# MCU.net
KiCad netlist of a schematic drawn in Altium Designer
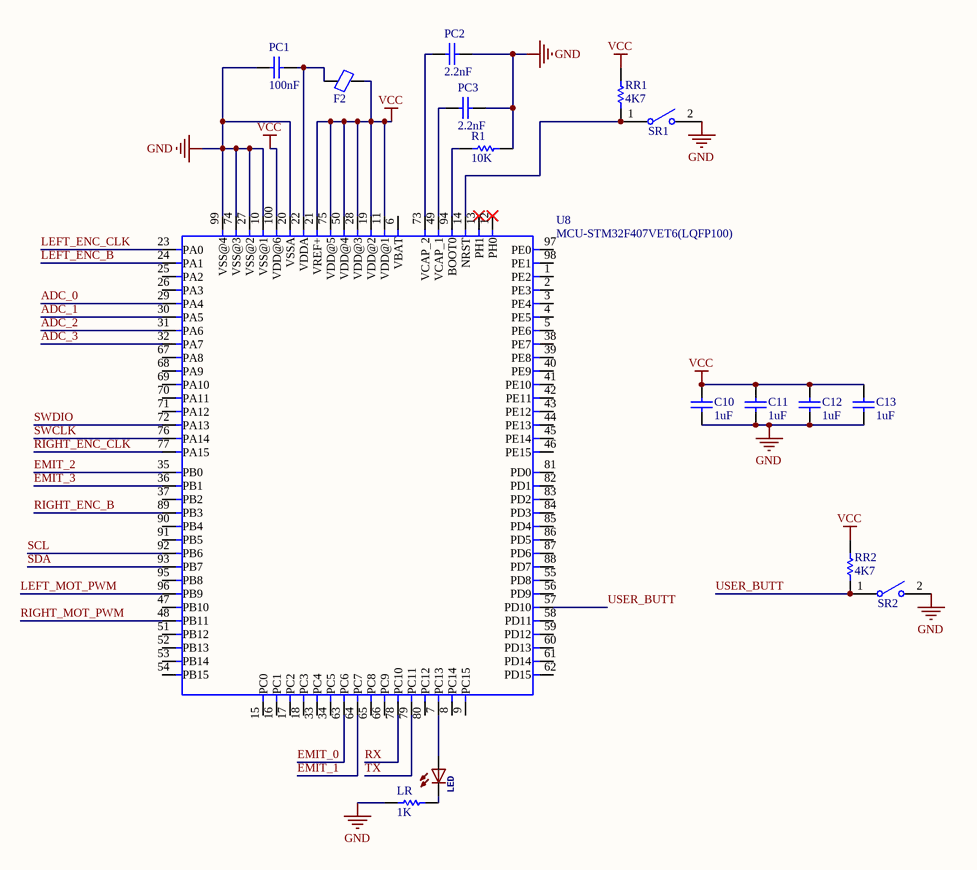
[diagram p0: MCU.SchDoc]

(export (version "E")
  (design (tool "Eeschema 10.0.6"))
  (components
    (comp (ref "C10")
      (value "1uF")
      (footprint "CAP0603")
      (description "0603 CAPACITOR SMD")
      (fields (field (name "DESIGNER") "Abbas Basereh"))
      (libsource (lib "Altium") (part "CAP SMD PACKAGE"))
    )
    (comp (ref "C11")
      (value "1uF")
      (footprint "CAP0603")
      (description "0603 CAPACITOR SMD")
      (fields (field (name "DESIGNER") "Abbas Basereh"))
      (libsource (lib "Altium") (part "CAP SMD PACKAGE"))
    )
    (comp (ref "C12")
      (value "1uF")
      (footprint "CAP0603")
      (description "0603 CAPACITOR SMD")
      (fields (field (name "DESIGNER") "Abbas Basereh"))
      (libsource (lib "Altium") (part "CAP SMD PACKAGE"))
    )
    (comp (ref "C13")
      (value "1uF")
      (footprint "CAP0603")
      (description "0603 CAPACITOR SMD")
      (fields (field (name "DESIGNER") "Abbas Basereh"))
      (libsource (lib "Altium") (part "CAP SMD PACKAGE"))
    )
    (comp (ref "F2")
      (value "Ferrite Bead SMD")
      (footprint "FB0603")
      (fields (field (name "DESIGNER") "Ali Hafizi"))
      (libsource (lib "Altium") (part "Ferrite Bead SMD Package"))
    )
    (comp (ref "LED")
      (value "LED   OSRAM: - CHIPLED LG R971, LG N971, LY N971, LG Q971, LY Q971, LO R971, LY R971 LH N974, LH R974 LS Q976, LO Q976, LY Q976 LO Q996 - Hyper CHIPLED LW Q18S LB Q993, LB Q99A, LB R99A - SideLED LS A670, LO A670, LY A670, LG A670, LP A670 LB A673, LV A673, LT A673, LW A673 LH A674 LY A675 LS A676, LA A676, LO A676, LY A676, LW A676 LS A679, LY A679, LG A679 -  Hyper Micro SIDELEDÂ® LS Y876, LA Y876, LO Y876, LY Y876 LT Y87S - SmartLED LW L88C, LW L88S LB L89C, LB L89S, LG L890 LS L89K, LO L89K, LY L89K LS L896, LA L896, LO L896, LY L896 - TOPLED LS T670, LO T670, LY T670, LG T670, LP T670 LSG T670, LSP T670, LSY T670, LOP T670, LYG T670 LG T671, LOG T671, LSG T671 LB T673, LV T673, LT T673, LW T673 LH T674 LS T676, LA T676, LO T676, LY T676, LB T676, LH T676, LSB T676, LW T676 LB T67C, LV T67C, LT T67C, LS T67K, LO T67K, LY T67K, LW E67C LS E67B, LA E67B, LO E67B, LY E67B, LB E67C, LV E67C, LT E67C LW T67C LS T679, LY T679, LG T679 LS T770, LO T770, LY T770, LG T770, LP T770 LB T773, LV T773, LT T773, LW T773 LH T774 LS E675, LA E675, LY E675, LS T675 LS T776, LA T776, LO T776, LY T776, LB T776 LHGB T686 LT T68C, LB T68C - Hyper Mini TOPLEDÂ® LB M676 - Mini TOPLED SantanaÂ® LG M470 LS M47K, LO M47K, LY M47K    Source: http://www.osram.convergy.de/")
      (footprint "CHIPLED_0603")
      (libsource (lib "adafruit") (part "LEDCHIPLED_0603"))
    )
    (comp (ref "LR")
      (value "1K")
      (footprint "RES0603")
      (description "TOTAL SMD RESISTOR PACK")
      (fields (field (name "DESIGNER") "Abbas Basereh"))
      (libsource (lib "Altium") (part "RES SMD PACKAGE"))
    )
    (comp (ref "PC1")
      (value "100nF")
      (footprint "CAP0603")
      (description "TOTAL CAPACITOR SMD PACK")
      (fields (field (name "DESIGNER") "Abbas Basereh"))
      (libsource (lib "Altium") (part "CAP SMD PACKAGE"))
    )
    (comp (ref "PC2")
      (value "2.2nF")
      (footprint "CAP0603")
      (description "TOTAL CAPACITOR SMD PACK")
      (fields (field (name "DESIGNER") "Abbas Basereh"))
      (libsource (lib "Altium") (part "CAP SMD PACKAGE"))
    )
    (comp (ref "PC3")
      (value "2.2nF")
      (footprint "CAP0603")
      (description "TOTAL CAPACITOR SMD PACK")
      (fields (field (name "DESIGNER") "Abbas Basereh"))
      (libsource (lib "Altium") (part "CAP SMD PACKAGE"))
    )
    (comp (ref "R1")
      (value "10K")
      (footprint "RES0603")
      (description "TOTAL SMD RESISTOR PACK")
      (fields (field (name "DESIGNER") "Abbas Basereh"))
      (libsource (lib "Altium") (part "RES SMD PACKAGE"))
    )
    (comp (ref "RR1")
      (value "4K7")
      (footprint "RES0603")
      (description "0603 RESISTOR")
      (fields (field (name "DESIGNER") "Abbas Basereh"))
      (libsource (lib "Altium") (part "RES SMD PACKAGE"))
    )
    (comp (ref "RR2")
      (value "4K7")
      (footprint "RES0603")
      (description "0603 RESISTOR")
      (fields (field (name "DESIGNER") "Abbas Basereh"))
      (libsource (lib "Altium") (part "RES SMD PACKAGE"))
    )
    (comp (ref "SR1")
      (value "434113050826")
      (footprint "4341x30508x6_6x3.5x5")
      (description "WS-TASV 6.0x3.5mm Tact Switch, J-Bend SMD version")
      (fields (field (name "PUBLISHER") "Wurth Elektronik"))
      (libsource (lib "Switch - Tactile SMT") (part "434113050826"))
    )
    (comp (ref "SR2")
      (value "434113050826")
      (footprint "4341x30508x6_6x3.5x5")
      (description "WS-TASV 6.0x3.5mm Tact Switch, J-Bend SMD version")
      (fields (field (name "PUBLISHER") "Wurth Elektronik"))
      (libsource (lib "Switch - Tactile SMT") (part "434113050826"))
    )
    (comp (ref "U8")
      (value "MCU-STM32F407VET6(LQFP100)")
      (footprint "LQFP100-0.5-13.8X13.8MM")
      (description "ARMÂ® CortexÂ®-M4 STM32F4 Microcontroller IC 32-Bit 168MHz 512KB _512K x 8_ FLASH 100-LQFP _14x14_")
      (fields (field (name "MF") "STMicroelectronics") (field (name "MP") "STM32F407VET6"))
      (libsource (lib "MCU-STM32F407VET6_LQFP100_") (part "MCU-STM32F407VET6(LQFP100)"))
    )
  )
  (nets
    (net (code "1") (name "/ADC_0") (class "Default")
      (node (ref "U8") (pin "29") (pinfunction "PA4_29") (pintype "bidirectional"))
    )
    (net (code "2") (name "/ADC_1") (class "Default")
      (node (ref "U8") (pin "30") (pinfunction "PA5_30") (pintype "bidirectional"))
    )
    (net (code "3") (name "/ADC_2") (class "Default")
      (node (ref "U8") (pin "31") (pinfunction "PA6_31") (pintype "bidirectional"))
    )
    (net (code "4") (name "/ADC_3") (class "Default")
      (node (ref "U8") (pin "32") (pinfunction "PA7_32") (pintype "bidirectional"))
    )
    (net (code "5") (name "/EMIT_0") (class "Default")
      (node (ref "U8") (pin "63") (pinfunction "PC6_63") (pintype "bidirectional"))
    )
    (net (code "6") (name "/EMIT_1") (class "Default")
      (node (ref "U8") (pin "64") (pinfunction "PC7_64") (pintype "bidirectional"))
    )
    (net (code "7") (name "/EMIT_2") (class "Default")
      (node (ref "U8") (pin "35") (pinfunction "PB0_35") (pintype "bidirectional"))
    )
    (net (code "8") (name "/EMIT_3") (class "Default")
      (node (ref "U8") (pin "36") (pinfunction "PB1_36") (pintype "bidirectional"))
    )
    (net (code "9") (name "/LEFT_ENC_B") (class "Default")
      (node (ref "U8") (pin "24") (pinfunction "PA1_24") (pintype "bidirectional"))
    )
    (net (code "10") (name "/LEFT_ENC_CLK") (class "Default")
      (node (ref "U8") (pin "23") (pinfunction "PA0_23") (pintype "bidirectional"))
    )
    (net (code "11") (name "/LEFT_MOT_PWM") (class "Default")
      (node (ref "U8") (pin "96") (pinfunction "PB9_96") (pintype "bidirectional"))
    )
    (net (code "12") (name "/RIGHT_ENC_B") (class "Default")
      (node (ref "U8") (pin "89") (pinfunction "PB3_89") (pintype "bidirectional"))
    )
    (net (code "13") (name "/RIGHT_ENC_CLK") (class "Default")
      (node (ref "U8") (pin "77") (pinfunction "PA15_77") (pintype "bidirectional"))
    )
    (net (code "14") (name "/RIGHT_MOT_PWM") (class "Default")
      (node (ref "U8") (pin "48") (pinfunction "PB11_48") (pintype "bidirectional"))
    )
    (net (code "15") (name "/RX") (class "Default")
      (node (ref "U8") (pin "78") (pinfunction "PC10_78") (pintype "bidirectional"))
    )
    (net (code "16") (name "/SCL") (class "Default")
      (node (ref "U8") (pin "92") (pinfunction "PB6_92") (pintype "bidirectional"))
    )
    (net (code "17") (name "/SDA") (class "Default")
      (node (ref "U8") (pin "93") (pinfunction "PB7_93") (pintype "bidirectional"))
    )
    (net (code "18") (name "/SWCLK") (class "Default")
      (node (ref "U8") (pin "76") (pinfunction "PA14_76") (pintype "bidirectional"))
    )
    (net (code "19") (name "/SWDIO") (class "Default")
      (node (ref "U8") (pin "72") (pinfunction "PA13_72") (pintype "bidirectional"))
    )
    (net (code "20") (name "/TX") (class "Default")
      (node (ref "U8") (pin "79") (pinfunction "PC11_79") (pintype "bidirectional"))
    )
    (net (code "21") (name "/USER_BUTT") (class "Default")
      (node (ref "RR2") (pin "1") (pinfunction "1_1") (pintype "passive"))
      (node (ref "SR2") (pin "1") (pinfunction "1_1") (pintype "passive"))
      (node (ref "U8") (pin "57") (pinfunction "PD10_57") (pintype "bidirectional"))
    )
    (net (code "22") (name "GND") (class "Default")
      (node (ref "C10") (pin "1") (pinfunction "1_1") (pintype "passive"))
      (node (ref "C11") (pin "1") (pinfunction "1_1") (pintype "passive"))
      (node (ref "C12") (pin "1") (pinfunction "1_1") (pintype "passive"))
      (node (ref "C13") (pin "1") (pinfunction "1_1") (pintype "passive"))
      (node (ref "LR") (pin "2") (pinfunction "2_2") (pintype "passive"))
      (node (ref "PC1") (pin "2") (pinfunction "2_2") (pintype "passive"))
      (node (ref "PC2") (pin "1") (pinfunction "1_1") (pintype "passive"))
      (node (ref "PC3") (pin "1") (pinfunction "1_1") (pintype "passive"))
      (node (ref "R1") (pin "1") (pinfunction "1_1") (pintype "passive"))
      (node (ref "SR1") (pin "2") (pinfunction "2_2") (pintype "passive"))
      (node (ref "SR2") (pin "2") (pinfunction "2_2") (pintype "passive"))
      (node (ref "U8") (pin "10") (pinfunction "VSS@1_10") (pintype "bidirectional"))
      (node (ref "U8") (pin "20") (pinfunction "VSSA_20") (pintype "bidirectional"))
      (node (ref "U8") (pin "27") (pinfunction "VSS@2_27") (pintype "bidirectional"))
      (node (ref "U8") (pin "74") (pinfunction "VSS@3_74") (pintype "bidirectional"))
      (node (ref "U8") (pin "99") (pinfunction "VSS@4_99") (pintype "bidirectional"))
    )
    (net (code "23") (name "Net-(LED-PadC)") (class "Default")
      (node (ref "LED") (pin "C") (pinfunction "C_C") (pintype "passive"))
      (node (ref "LR") (pin "1") (pinfunction "1_1") (pintype "passive"))
    )
    (net (code "24") (name "Net-(U8-BOOT0)") (class "Default")
      (node (ref "R1") (pin "2") (pinfunction "2_2") (pintype "passive"))
      (node (ref "U8") (pin "94") (pinfunction "BOOT0_94") (pintype "bidirectional"))
    )
    (net (code "25") (name "Net-(U8-NRST)") (class "Default")
      (node (ref "RR1") (pin "1") (pinfunction "1_1") (pintype "passive"))
      (node (ref "SR1") (pin "1") (pinfunction "1_1") (pintype "passive"))
      (node (ref "U8") (pin "14") (pinfunction "NRST_14") (pintype "bidirectional"))
    )
    (net (code "26") (name "Net-(U8-PC13)") (class "Default")
      (node (ref "LED") (pin "A") (pinfunction "A_A") (pintype "passive"))
      (node (ref "U8") (pin "7") (pinfunction "PC13_7") (pintype "bidirectional"))
    )
    (net (code "27") (name "Net-(U8-VCAP_1)") (class "Default")
      (node (ref "PC3") (pin "2") (pinfunction "2_2") (pintype "passive"))
      (node (ref "U8") (pin "49") (pinfunction "VCAP_1_49") (pintype "bidirectional"))
    )
    (net (code "28") (name "Net-(U8-VCAP_2)") (class "Default")
      (node (ref "PC2") (pin "2") (pinfunction "2_2") (pintype "passive"))
      (node (ref "U8") (pin "73") (pinfunction "VCAP_2_73") (pintype "bidirectional"))
    )
    (net (code "29") (name "Net-(U8-VDDA)") (class "Default")
      (node (ref "F2") (pin "1") (pinfunction "1_1") (pintype "passive"))
      (node (ref "PC1") (pin "1") (pinfunction "1_1") (pintype "passive"))
      (node (ref "U8") (pin "22") (pinfunction "VDDA_22") (pintype "bidirectional"))
    )
    (net (code "30") (name "VCC") (class "Default")
      (node (ref "C10") (pin "2") (pinfunction "2_2") (pintype "passive"))
      (node (ref "C11") (pin "2") (pinfunction "2_2") (pintype "passive"))
      (node (ref "C12") (pin "2") (pinfunction "2_2") (pintype "passive"))
      (node (ref "C13") (pin "2") (pinfunction "2_2") (pintype "passive"))
      (node (ref "F2") (pin "2") (pinfunction "2_2") (pintype "passive"))
      (node (ref "RR1") (pin "2") (pinfunction "2_2") (pintype "passive"))
      (node (ref "RR2") (pin "2") (pinfunction "2_2") (pintype "passive"))
      (node (ref "U8") (pin "100") (pinfunction "VDD@6_100") (pintype "bidirectional"))
      (node (ref "U8") (pin "11") (pinfunction "VDD@1_11") (pintype "bidirectional"))
      (node (ref "U8") (pin "19") (pinfunction "VDD@2_19") (pintype "bidirectional"))
      (node (ref "U8") (pin "21") (pinfunction "VREF+_21") (pintype "bidirectional"))
      (node (ref "U8") (pin "28") (pinfunction "VDD@3_28") (pintype "bidirectional"))
      (node (ref "U8") (pin "50") (pinfunction "VDD@4_50") (pintype "bidirectional"))
      (node (ref "U8") (pin "75") (pinfunction "VDD@5_75") (pintype "bidirectional"))
    )
    (net (code "31") (name "unconnected-(U8-PA2-Pad25)") (class "Default")
      (node (ref "U8") (pin "25") (pinfunction "PA2_25") (pintype "bidirectional"))
    )
    (net (code "32") (name "unconnected-(U8-PA3-Pad26)") (class "Default")
      (node (ref "U8") (pin "26") (pinfunction "PA3_26") (pintype "bidirectional"))
    )
    (net (code "33") (name "unconnected-(U8-PA8-Pad67)") (class "Default")
      (node (ref "U8") (pin "67") (pinfunction "PA8_67") (pintype "bidirectional"))
    )
    (net (code "34") (name "unconnected-(U8-PA9-Pad68)") (class "Default")
      (node (ref "U8") (pin "68") (pinfunction "PA9_68") (pintype "bidirectional"))
    )
    (net (code "35") (name "unconnected-(U8-PA10-Pad69)") (class "Default")
      (node (ref "U8") (pin "69") (pinfunction "PA10_69") (pintype "bidirectional"))
    )
    (net (code "36") (name "unconnected-(U8-PA11-Pad70)") (class "Default")
      (node (ref "U8") (pin "70") (pinfunction "PA11_70") (pintype "bidirectional"))
    )
    (net (code "37") (name "unconnected-(U8-PA12-Pad71)") (class "Default")
      (node (ref "U8") (pin "71") (pinfunction "PA12_71") (pintype "bidirectional"))
    )
    (net (code "38") (name "unconnected-(U8-PB2-Pad37)") (class "Default")
      (node (ref "U8") (pin "37") (pinfunction "PB2_37") (pintype "bidirectional"))
    )
    (net (code "39") (name "unconnected-(U8-PB4-Pad90)") (class "Default")
      (node (ref "U8") (pin "90") (pinfunction "PB4_90") (pintype "bidirectional"))
    )
    (net (code "40") (name "unconnected-(U8-PB5-Pad91)") (class "Default")
      (node (ref "U8") (pin "91") (pinfunction "PB5_91") (pintype "bidirectional"))
    )
    (net (code "41") (name "unconnected-(U8-PB8-Pad95)") (class "Default")
      (node (ref "U8") (pin "95") (pinfunction "PB8_95") (pintype "bidirectional"))
    )
    (net (code "42") (name "unconnected-(U8-PB10-Pad47)") (class "Default")
      (node (ref "U8") (pin "47") (pinfunction "PB10_47") (pintype "bidirectional"))
    )
    (net (code "43") (name "unconnected-(U8-PB12-Pad51)") (class "Default")
      (node (ref "U8") (pin "51") (pinfunction "PB12_51") (pintype "bidirectional"))
    )
    (net (code "44") (name "unconnected-(U8-PB13-Pad52)") (class "Default")
      (node (ref "U8") (pin "52") (pinfunction "PB13_52") (pintype "bidirectional"))
    )
    (net (code "45") (name "unconnected-(U8-PB14-Pad53)") (class "Default")
      (node (ref "U8") (pin "53") (pinfunction "PB14_53") (pintype "bidirectional"))
    )
    (net (code "46") (name "unconnected-(U8-PB15-Pad54)") (class "Default")
      (node (ref "U8") (pin "54") (pinfunction "PB15_54") (pintype "bidirectional"))
    )
    (net (code "47") (name "unconnected-(U8-PC0-Pad15)") (class "Default")
      (node (ref "U8") (pin "15") (pinfunction "PC0_15") (pintype "bidirectional"))
    )
    (net (code "48") (name "unconnected-(U8-PC1-Pad16)") (class "Default")
      (node (ref "U8") (pin "16") (pinfunction "PC1_16") (pintype "bidirectional"))
    )
    (net (code "49") (name "unconnected-(U8-PC2-Pad17)") (class "Default")
      (node (ref "U8") (pin "17") (pinfunction "PC2_17") (pintype "bidirectional"))
    )
    (net (code "50") (name "unconnected-(U8-PC3-Pad18)") (class "Default")
      (node (ref "U8") (pin "18") (pinfunction "PC3_18") (pintype "bidirectional"))
    )
    (net (code "51") (name "unconnected-(U8-PC4-Pad33)") (class "Default")
      (node (ref "U8") (pin "33") (pinfunction "PC4_33") (pintype "bidirectional"))
    )
    (net (code "52") (name "unconnected-(U8-PC5-Pad34)") (class "Default")
      (node (ref "U8") (pin "34") (pinfunction "PC5_34") (pintype "bidirectional"))
    )
    (net (code "53") (name "unconnected-(U8-PC8-Pad65)") (class "Default")
      (node (ref "U8") (pin "65") (pinfunction "PC8_65") (pintype "bidirectional"))
    )
    (net (code "54") (name "unconnected-(U8-PC9-Pad66)") (class "Default")
      (node (ref "U8") (pin "66") (pinfunction "PC9_66") (pintype "bidirectional"))
    )
    (net (code "55") (name "unconnected-(U8-PC12-Pad80)") (class "Default")
      (node (ref "U8") (pin "80") (pinfunction "PC12_80") (pintype "bidirectional"))
    )
    (net (code "56") (name "unconnected-(U8-PC14-Pad8)") (class "Default")
      (node (ref "U8") (pin "8") (pinfunction "PC14_8") (pintype "bidirectional"))
    )
    (net (code "57") (name "unconnected-(U8-PC15-Pad9)") (class "Default")
      (node (ref "U8") (pin "9") (pinfunction "PC15_9") (pintype "bidirectional"))
    )
    (net (code "58") (name "unconnected-(U8-PD0-Pad81)") (class "Default")
      (node (ref "U8") (pin "81") (pinfunction "PD0_81") (pintype "bidirectional"))
    )
    (net (code "59") (name "unconnected-(U8-PD1-Pad82)") (class "Default")
      (node (ref "U8") (pin "82") (pinfunction "PD1_82") (pintype "bidirectional"))
    )
    (net (code "60") (name "unconnected-(U8-PD2-Pad83)") (class "Default")
      (node (ref "U8") (pin "83") (pinfunction "PD2_83") (pintype "bidirectional"))
    )
    (net (code "61") (name "unconnected-(U8-PD3-Pad84)") (class "Default")
      (node (ref "U8") (pin "84") (pinfunction "PD3_84") (pintype "bidirectional"))
    )
    (net (code "62") (name "unconnected-(U8-PD4-Pad85)") (class "Default")
      (node (ref "U8") (pin "85") (pinfunction "PD4_85") (pintype "bidirectional"))
    )
    (net (code "63") (name "unconnected-(U8-PD5-Pad86)") (class "Default")
      (node (ref "U8") (pin "86") (pinfunction "PD5_86") (pintype "bidirectional"))
    )
    (net (code "64") (name "unconnected-(U8-PD6-Pad87)") (class "Default")
      (node (ref "U8") (pin "87") (pinfunction "PD6_87") (pintype "bidirectional"))
    )
    (net (code "65") (name "unconnected-(U8-PD7-Pad88)") (class "Default")
      (node (ref "U8") (pin "88") (pinfunction "PD7_88") (pintype "bidirectional"))
    )
    (net (code "66") (name "unconnected-(U8-PD8-Pad55)") (class "Default")
      (node (ref "U8") (pin "55") (pinfunction "PD8_55") (pintype "bidirectional"))
    )
    (net (code "67") (name "unconnected-(U8-PD9-Pad56)") (class "Default")
      (node (ref "U8") (pin "56") (pinfunction "PD9_56") (pintype "bidirectional"))
    )
    (net (code "68") (name "unconnected-(U8-PD11-Pad58)") (class "Default")
      (node (ref "U8") (pin "58") (pinfunction "PD11_58") (pintype "bidirectional"))
    )
    (net (code "69") (name "unconnected-(U8-PD12-Pad59)") (class "Default")
      (node (ref "U8") (pin "59") (pinfunction "PD12_59") (pintype "bidirectional"))
    )
    (net (code "70") (name "unconnected-(U8-PD13-Pad60)") (class "Default")
      (node (ref "U8") (pin "60") (pinfunction "PD13_60") (pintype "bidirectional"))
    )
    (net (code "71") (name "unconnected-(U8-PD14-Pad61)") (class "Default")
      (node (ref "U8") (pin "61") (pinfunction "PD14_61") (pintype "bidirectional"))
    )
    (net (code "72") (name "unconnected-(U8-PD15-Pad62)") (class "Default")
      (node (ref "U8") (pin "62") (pinfunction "PD15_62") (pintype "bidirectional"))
    )
    (net (code "73") (name "unconnected-(U8-PE0-Pad97)") (class "Default")
      (node (ref "U8") (pin "97") (pinfunction "PE0_97") (pintype "bidirectional"))
    )
    (net (code "74") (name "unconnected-(U8-PE1-Pad98)") (class "Default")
      (node (ref "U8") (pin "98") (pinfunction "PE1_98") (pintype "bidirectional"))
    )
    (net (code "75") (name "unconnected-(U8-PE2-Pad1)") (class "Default")
      (node (ref "U8") (pin "1") (pinfunction "PE2_1") (pintype "bidirectional"))
    )
    (net (code "76") (name "unconnected-(U8-PE3-Pad2)") (class "Default")
      (node (ref "U8") (pin "2") (pinfunction "PE3_2") (pintype "bidirectional"))
    )
    (net (code "77") (name "unconnected-(U8-PE4-Pad3)") (class "Default")
      (node (ref "U8") (pin "3") (pinfunction "PE4_3") (pintype "bidirectional"))
    )
    (net (code "78") (name "unconnected-(U8-PE5-Pad4)") (class "Default")
      (node (ref "U8") (pin "4") (pinfunction "PE5_4") (pintype "bidirectional"))
    )
    (net (code "79") (name "unconnected-(U8-PE6-Pad5)") (class "Default")
      (node (ref "U8") (pin "5") (pinfunction "PE6_5") (pintype "bidirectional"))
    )
    (net (code "80") (name "unconnected-(U8-PE7-Pad38)") (class "Default")
      (node (ref "U8") (pin "38") (pinfunction "PE7_38") (pintype "bidirectional"))
    )
    (net (code "81") (name "unconnected-(U8-PE8-Pad39)") (class "Default")
      (node (ref "U8") (pin "39") (pinfunction "PE8_39") (pintype "bidirectional"))
    )
    (net (code "82") (name "unconnected-(U8-PE9-Pad40)") (class "Default")
      (node (ref "U8") (pin "40") (pinfunction "PE9_40") (pintype "bidirectional"))
    )
    (net (code "83") (name "unconnected-(U8-PE10-Pad41)") (class "Default")
      (node (ref "U8") (pin "41") (pinfunction "PE10_41") (pintype "bidirectional"))
    )
    (net (code "84") (name "unconnected-(U8-PE11-Pad42)") (class "Default")
      (node (ref "U8") (pin "42") (pinfunction "PE11_42") (pintype "bidirectional"))
    )
    (net (code "85") (name "unconnected-(U8-PE12-Pad43)") (class "Default")
      (node (ref "U8") (pin "43") (pinfunction "PE12_43") (pintype "bidirectional"))
    )
    (net (code "86") (name "unconnected-(U8-PE13-Pad44)") (class "Default")
      (node (ref "U8") (pin "44") (pinfunction "PE13_44") (pintype "bidirectional"))
    )
    (net (code "87") (name "unconnected-(U8-PE14-Pad45)") (class "Default")
      (node (ref "U8") (pin "45") (pinfunction "PE14_45") (pintype "bidirectional"))
    )
    (net (code "88") (name "unconnected-(U8-PE15-Pad46)") (class "Default")
      (node (ref "U8") (pin "46") (pinfunction "PE15_46") (pintype "bidirectional"))
    )
    (net (code "89") (name "unconnected-(U8-PH0-Pad12)") (class "Default")
      (node (ref "U8") (pin "12") (pinfunction "PH0_12") (pintype "bidirectional+no_connect"))
    )
    (net (code "90") (name "unconnected-(U8-PH1-Pad13)") (class "Default")
      (node (ref "U8") (pin "13") (pinfunction "PH1_13") (pintype "bidirectional+no_connect"))
    )
    (net (code "91") (name "unconnected-(U8-VBAT-Pad6)") (class "Default")
      (node (ref "U8") (pin "6") (pinfunction "VBAT_6") (pintype "bidirectional"))
    )
  )
)
